# Power_Distribution.net
KiCad netlist of a schematic drawn in Altium Designer
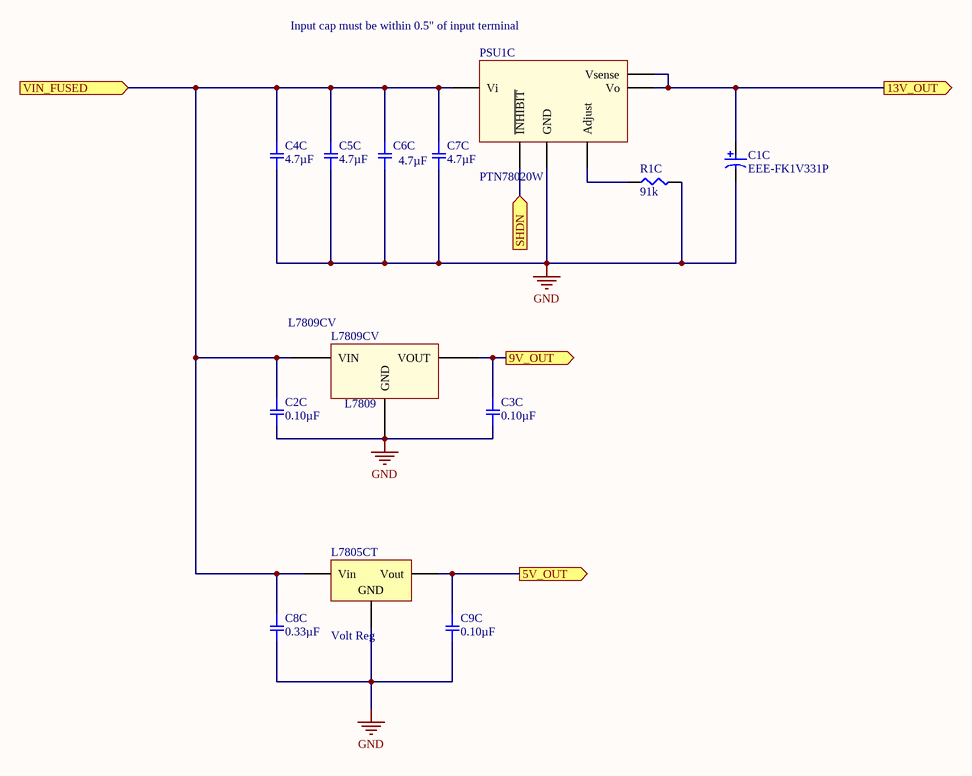
[diagram p0: Power Distribution.SchDoc]

(export (version "E")
  (design (tool "Eeschema 10.0.6"))
  (components
    (comp (ref "C1C")
      (value "EEE-FK1V331P")
      (footprint "PNSC-EEE-FK1V331P_L")
      (description "Aluminum Electrolytic Capacitor, 330 uF, 35 V, -55 to 105 degC, 2-Pin CAPAE, RoHS, Tape and Reel")
      (fields (field (name "MANUFACTURER") "Panasonic"))
      (libsource (lib "Altium Content Vault") (part "CAP-P-2"))
    )
    (comp (ref "C2C")
      (value "0.10µF")
      (footprint "SMD-1206C")
      (description "CAP CER 0.1UF 250V X7R 1206")
      (fields
        (field (name "DIGI-KEY PART NUMBER") "490-12647-1-ND")
        (field (name "PART NUMBER") "GCJ31CR72E104KXJ3L")
      )
      (libsource (lib "capacitor_murata_1206") (part "GCJ31CR72E104KXJ3L"))
    )
    (comp (ref "C3C")
      (value "0.10µF")
      (footprint "SMD-1206C")
      (description "CAP CER 0.1UF 250V X7R 1206")
      (fields
        (field (name "DIGI-KEY PART NUMBER") "490-12647-1-ND")
        (field (name "PART NUMBER") "GCJ31CR72E104KXJ3L")
      )
      (libsource (lib "capacitor_murata_1206") (part "GCJ31CR72E104KXJ3L"))
    )
    (comp (ref "C4C")
      (value "4.7µF")
      (footprint "SMD-1206C")
      (description "CAP CER 4.7UF 50V X7S 1206")
      (fields
        (field (name "DIGI-KEY PART NUMBER") "490-11167-1-ND")
        (field (name "PART NUMBER") "GCM31CC71H475KA03L")
      )
      (libsource (lib "capacitor_murata_1206") (part "GCM31CC71H475KA03L"))
    )
    (comp (ref "C5C")
      (value "4.7µF")
      (footprint "SMD-1206C")
      (description "CAP CER 4.7UF 50V X7S 1206")
      (fields
        (field (name "DIGI-KEY PART NUMBER") "490-11167-1-ND")
        (field (name "PART NUMBER") "GCM31CC71H475KA03L")
      )
      (libsource (lib "capacitor_murata_1206") (part "GCM31CC71H475KA03L"))
    )
    (comp (ref "C6C")
      (value "4.7µF")
      (footprint "SMD-1206C")
      (description "CAP CER 4.7UF 50V X7S 1206")
      (fields
        (field (name "DIGI-KEY PART NUMBER") "490-11167-1-ND")
        (field (name "PART NUMBER") "GCM31CC71H475KA03L")
      )
      (libsource (lib "capacitor_murata_1206") (part "GCM31CC71H475KA03L"))
    )
    (comp (ref "C7C")
      (value "4.7µF")
      (footprint "SMD-1206C")
      (description "CAP CER 4.7UF 50V X7S 1206")
      (fields
        (field (name "DIGI-KEY PART NUMBER") "490-11167-1-ND")
        (field (name "PART NUMBER") "GCM31CC71H475KA03L")
      )
      (libsource (lib "capacitor_murata_1206") (part "GCM31CC71H475KA03L"))
    )
    (comp (ref "C8C")
      (value "0.33µF")
      (footprint "SMD-1206C")
      (description "CAP CER 0.33UF 50V X7R 1206")
      (fields
        (field (name "DIGI-KEY PART NUMBER") "490-8060-1-ND")
        (field (name "PART NUMBER") "GCM31MR71H334KA37L")
      )
      (libsource (lib "capacitor_murata_1206") (part "GCM31MR71H334KA37L"))
    )
    (comp (ref "C9C")
      (value "0.10µF")
      (footprint "SMD-1206C")
      (description "CAP CER 0.1UF 50V X7R 1206")
      (fields
        (field (name "DIGI-KEY PART NUMBER") "490-10930-1-ND")
        (field (name "PART NUMBER") "GRJ319R71H104KE11L")
      )
      (libsource (lib "capacitor_murata_1206") (part "GRJ319R71H104KE11L"))
    )
    (comp (ref "L7805CT")
      (value "Volt Reg")
      (footprint "D2PAK_N")
      (description "Voltage Regulator")
      (fields (field (name "PUBLISHER") "Altium Limited"))
      (libsource (lib "Miscellaneous Devices") (part "Volt Reg"))
    )
    (comp (ref "L7809CV")
      (value "L7809")
      (footprint "L7809CD2T-D2PAK")
      (fields
        (field (name "MANUFACTURER") "STMICROELECTRONICS")
        (field (name "MANUFACTURER PART NUMBER") "L7809CV")
      )
      (libsource (lib "URC") (part "L7809"))
    )
    (comp (ref "PSU1C")
      (value "PTN78020W")
      (footprint "PTN78020")
      (description "Adjustable, non-isolating DC-DC converter")
      (libsource (lib "URC_Lib") (part "PTN78020W"))
    )
    (comp (ref "R1C")
      (value "91k")
      (footprint "SMD-1206-RES")
      (description "RES SMD 91K OHM 5% 1/4W 1206")
      (fields (field (name "PART NUMBER") "ERJ-8GEYJ913V") (field (name "DIGI-KEY PART NUMBER") "P91KECT-ND"))
      (libsource (lib "Panasonic_ERJ_1206") (part "ERJ-8GEYJ913V"))
    )
  )
  (nets
    (net (code "1") (name "/5V_OUT") (class "Default")
      (node (ref "C9C") (pin "1") (pinfunction "1_1") (pintype "passive"))
      (node (ref "L7805CT") (pin "3") (pinfunction "Vout_3") (pintype "passive"))
    )
    (net (code "2") (name "/9V_OUT") (class "Default")
      (node (ref "C3C") (pin "1") (pinfunction "1_1") (pintype "passive"))
      (node (ref "L7809CV") (pin "OUTPUT") (pinfunction "VOUT_OUTPUT") (pintype "passive"))
    )
    (net (code "3") (name "/13V_OUT") (class "Default")
      (node (ref "C1C") (pin "1") (pinfunction "1_1") (pintype "passive"))
      (node (ref "PSU1C") (pin "Vsense") (pinfunction "Vsense_Vsense") (pintype "passive"))
      (node (ref "PSU1C") (pin "vo") (pinfunction "Vo_vo") (pintype "passive"))
    )
    (net (code "4") (name "/SHDN") (class "Default")
      (node (ref "PSU1C") (pin "INHIBIT") (pinfunction "~{INHIBIT}_INHIBIT") (pintype "passive"))
    )
    (net (code "5") (name "/VIN_FUSED") (class "Default")
      (node (ref "C2C") (pin "1") (pinfunction "1_1") (pintype "passive"))
      (node (ref "C4C") (pin "1") (pinfunction "1_1") (pintype "passive"))
      (node (ref "C5C") (pin "1") (pinfunction "1_1") (pintype "passive"))
      (node (ref "C6C") (pin "1") (pinfunction "1_1") (pintype "passive"))
      (node (ref "C7C") (pin "1") (pinfunction "1_1") (pintype "passive"))
      (node (ref "C8C") (pin "1") (pinfunction "1_1") (pintype "passive"))
      (node (ref "L7805CT") (pin "1") (pinfunction "Vin_1") (pintype "passive"))
      (node (ref "L7809CV") (pin "INPUT") (pinfunction "VIN_INPUT") (pintype "passive"))
      (node (ref "PSU1C") (pin "VIN") (pinfunction "Vi_VIN") (pintype "passive"))
    )
    (net (code "6") (name "GND") (class "Default")
      (node (ref "C1C") (pin "2") (pinfunction "2_2") (pintype "passive"))
      (node (ref "C2C") (pin "2") (pinfunction "2_2") (pintype "passive"))
      (node (ref "C3C") (pin "2") (pinfunction "2_2") (pintype "passive"))
      (node (ref "C4C") (pin "2") (pinfunction "2_2") (pintype "passive"))
      (node (ref "C5C") (pin "2") (pinfunction "2_2") (pintype "passive"))
      (node (ref "C6C") (pin "2") (pinfunction "2_2") (pintype "passive"))
      (node (ref "C7C") (pin "2") (pinfunction "2_2") (pintype "passive"))
      (node (ref "C8C") (pin "2") (pinfunction "2_2") (pintype "passive"))
      (node (ref "C9C") (pin "2") (pinfunction "2_2") (pintype "passive"))
      (node (ref "L7805CT") (pin "2") (pinfunction "GND_2") (pintype "passive"))
      (node (ref "L7809CV") (pin "GND") (pinfunction "GND_GND") (pintype "passive"))
      (node (ref "PSU1C") (pin "GND") (pinfunction "GND_GND") (pintype "passive"))
      (node (ref "R1C") (pin "2") (pinfunction "2_2") (pintype "passive"))
    )
    (net (code "7") (name "Net-(PSU1C-Adjust)") (class "Default")
      (node (ref "PSU1C") (pin "Rset") (pinfunction "Adjust_Rset") (pintype "passive"))
      (node (ref "R1C") (pin "1") (pinfunction "1_1") (pintype "passive"))
    )
  )
)
